# RAM.net
KiCad netlist of a schematic drawn in EAGLE
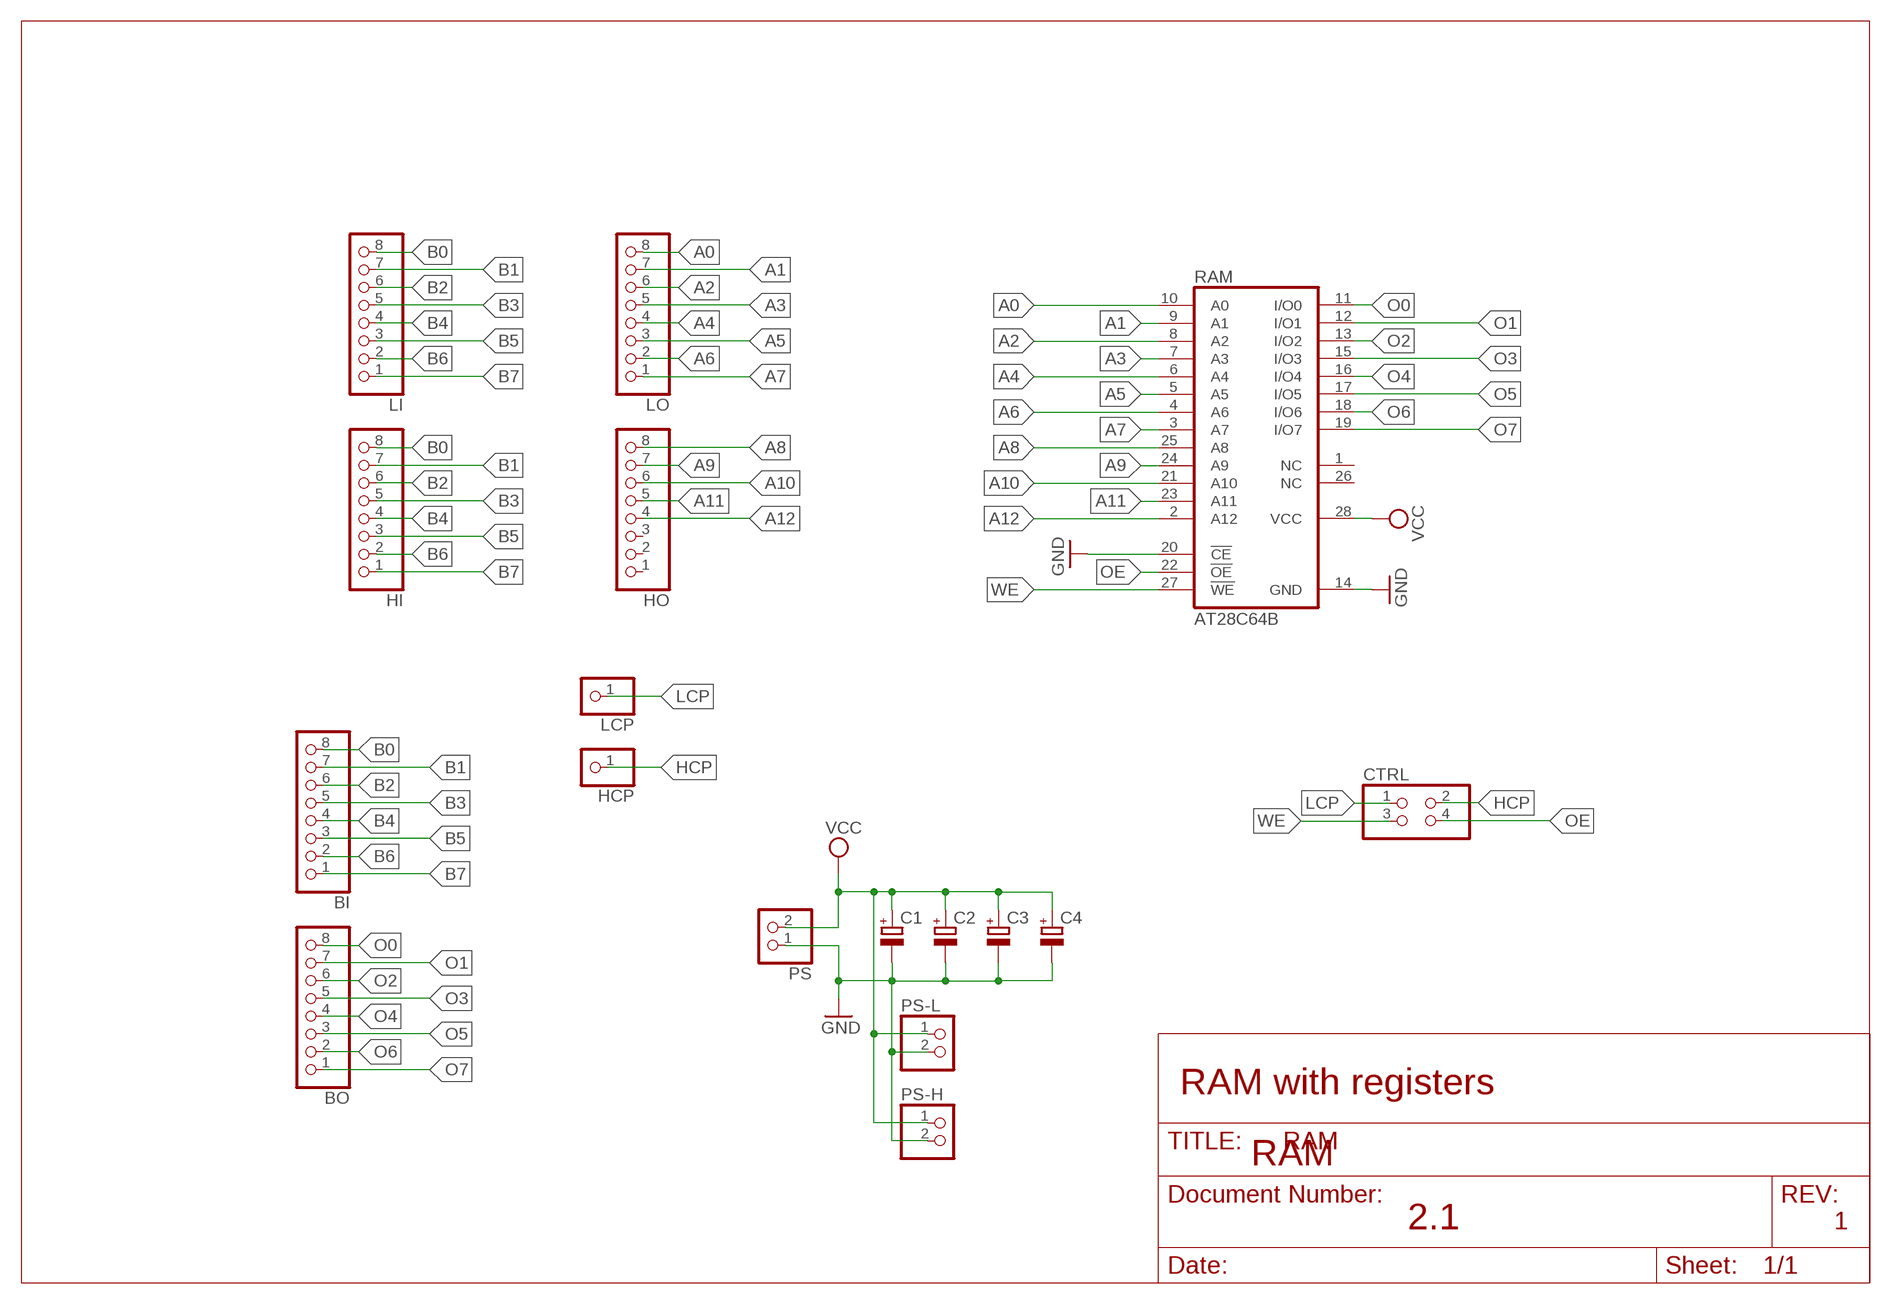
[diagram p0: schematic, sheet 1]

(export (version "E")
  (design (tool "Eeschema 10.0.6"))
  (components
    (comp (ref "BI")
      (value "PINHD-1X8")
      (footprint "eagle-import:1X08")
      (libsource (lib "eagle-import") (part "PINHD-1X8"))
    )
    (comp (ref "BO")
      (value "PINHD-1X8")
      (footprint "eagle-import:1X08")
      (libsource (lib "eagle-import") (part "PINHD-1X8"))
    )
    (comp (ref "C1")
      (value "CPOL-EUE2.5-6")
      (footprint "eagle-import:E2,5-6")
      (libsource (lib "eagle-import") (part "CPOL-EUE2.5-6"))
    )
    (comp (ref "C2")
      (value "CPOL-EUE2.5-6")
      (footprint "eagle-import:E2,5-6")
      (libsource (lib "eagle-import") (part "CPOL-EUE2.5-6"))
    )
    (comp (ref "C3")
      (value "CPOL-EUE2.5-6")
      (footprint "eagle-import:E2,5-6")
      (libsource (lib "eagle-import") (part "CPOL-EUE2.5-6"))
    )
    (comp (ref "C4")
      (value "CPOL-EUE2.5-6")
      (footprint "eagle-import:E2,5-6")
      (libsource (lib "eagle-import") (part "CPOL-EUE2.5-6"))
    )
    (comp (ref "CTRL")
      (value "PINHD-2X2")
      (footprint "eagle-import:2X02")
      (libsource (lib "eagle-import") (part "PINHD-2X2"))
    )
    (comp (ref "HCP")
      (value "PINHD-1X1")
      (footprint "eagle-import:1X01")
      (libsource (lib "eagle-import") (part "PINHD-1X1"))
    )
    (comp (ref "HI")
      (value "PINHD-1X8")
      (footprint "eagle-import:1X08")
      (libsource (lib "eagle-import") (part "PINHD-1X8"))
    )
    (comp (ref "HO")
      (value "PINHD-1X8")
      (footprint "eagle-import:1X08")
      (libsource (lib "eagle-import") (part "PINHD-1X8"))
    )
    (comp (ref "LCP")
      (value "PINHD-1X1")
      (footprint "eagle-import:1X01")
      (libsource (lib "eagle-import") (part "PINHD-1X1"))
    )
    (comp (ref "LI")
      (value "PINHD-1X8")
      (footprint "eagle-import:1X08")
      (libsource (lib "eagle-import") (part "PINHD-1X8"))
    )
    (comp (ref "LO")
      (value "PINHD-1X8")
      (footprint "eagle-import:1X08")
      (libsource (lib "eagle-import") (part "PINHD-1X8"))
    )
    (comp (ref "PS")
      (value "PINHD-1X2")
      (footprint "eagle-import:1X02")
      (libsource (lib "eagle-import") (part "PINHD-1X2"))
    )
    (comp (ref "PS-H")
      (value "PINHD-1X2")
      (footprint "eagle-import:1X02")
      (libsource (lib "eagle-import") (part "PINHD-1X2"))
    )
    (comp (ref "PS-L")
      (value "PINHD-1X2")
      (footprint "eagle-import:1X02")
      (libsource (lib "eagle-import") (part "PINHD-1X2"))
    )
    (comp (ref "RAM")
      (value "AT28C64B")
      (footprint "eagle-import:DIL28-6")
      (fields (field (name "MPN") "AT28C64B-15PU"))
      (libsource (lib "eagle-import") (part "28C64C"))
    )
  )
  (nets
    (net (code "1") (name "A0") (class "Default")
      (node (ref "LO") (pin "8") (pinfunction "8_8") (pintype "passive"))
      (node (ref "RAM") (pin "10") (pinfunction "A0_10") (pintype "input"))
    )
    (net (code "2") (name "A1") (class "Default")
      (node (ref "LO") (pin "7") (pinfunction "7_7") (pintype "passive"))
      (node (ref "RAM") (pin "9") (pinfunction "A1_9") (pintype "input"))
    )
    (net (code "3") (name "A2") (class "Default")
      (node (ref "LO") (pin "6") (pinfunction "6_6") (pintype "passive"))
      (node (ref "RAM") (pin "8") (pinfunction "A2_8") (pintype "input"))
    )
    (net (code "4") (name "A3") (class "Default")
      (node (ref "LO") (pin "5") (pinfunction "5_5") (pintype "passive"))
      (node (ref "RAM") (pin "7") (pinfunction "A3_7") (pintype "input"))
    )
    (net (code "5") (name "A4") (class "Default")
      (node (ref "LO") (pin "4") (pinfunction "4_4") (pintype "passive"))
      (node (ref "RAM") (pin "6") (pinfunction "A4_6") (pintype "input"))
    )
    (net (code "6") (name "A5") (class "Default")
      (node (ref "LO") (pin "3") (pinfunction "3_3") (pintype "passive"))
      (node (ref "RAM") (pin "5") (pinfunction "A5_5") (pintype "input"))
    )
    (net (code "7") (name "A6") (class "Default")
      (node (ref "LO") (pin "2") (pinfunction "2_2") (pintype "passive"))
      (node (ref "RAM") (pin "4") (pinfunction "A6_4") (pintype "input"))
    )
    (net (code "8") (name "A7") (class "Default")
      (node (ref "LO") (pin "1") (pinfunction "1_1") (pintype "passive"))
      (node (ref "RAM") (pin "3") (pinfunction "A7_3") (pintype "input"))
    )
    (net (code "9") (name "A8") (class "Default")
      (node (ref "HO") (pin "8") (pinfunction "8_8") (pintype "passive"))
      (node (ref "RAM") (pin "25") (pinfunction "A8_25") (pintype "input"))
    )
    (net (code "10") (name "A9") (class "Default")
      (node (ref "HO") (pin "7") (pinfunction "7_7") (pintype "passive"))
      (node (ref "RAM") (pin "24") (pinfunction "A9_24") (pintype "input"))
    )
    (net (code "11") (name "A10") (class "Default")
      (node (ref "HO") (pin "6") (pinfunction "6_6") (pintype "passive"))
      (node (ref "RAM") (pin "21") (pinfunction "A10_21") (pintype "input"))
    )
    (net (code "12") (name "A11") (class "Default")
      (node (ref "HO") (pin "5") (pinfunction "5_5") (pintype "passive"))
      (node (ref "RAM") (pin "23") (pinfunction "A11_23") (pintype "input"))
    )
    (net (code "13") (name "A12") (class "Default")
      (node (ref "HO") (pin "4") (pinfunction "4_4") (pintype "passive"))
      (node (ref "RAM") (pin "2") (pinfunction "A12_2") (pintype "input"))
    )
    (net (code "14") (name "B0") (class "Default")
      (node (ref "BI") (pin "8") (pinfunction "8_8") (pintype "passive"))
      (node (ref "HI") (pin "8") (pinfunction "8_8") (pintype "passive"))
      (node (ref "LI") (pin "8") (pinfunction "8_8") (pintype "passive"))
    )
    (net (code "15") (name "B1") (class "Default")
      (node (ref "BI") (pin "7") (pinfunction "7_7") (pintype "passive"))
      (node (ref "HI") (pin "7") (pinfunction "7_7") (pintype "passive"))
      (node (ref "LI") (pin "7") (pinfunction "7_7") (pintype "passive"))
    )
    (net (code "16") (name "B2") (class "Default")
      (node (ref "BI") (pin "6") (pinfunction "6_6") (pintype "passive"))
      (node (ref "HI") (pin "6") (pinfunction "6_6") (pintype "passive"))
      (node (ref "LI") (pin "6") (pinfunction "6_6") (pintype "passive"))
    )
    (net (code "17") (name "B3") (class "Default")
      (node (ref "BI") (pin "5") (pinfunction "5_5") (pintype "passive"))
      (node (ref "HI") (pin "5") (pinfunction "5_5") (pintype "passive"))
      (node (ref "LI") (pin "5") (pinfunction "5_5") (pintype "passive"))
    )
    (net (code "18") (name "B4") (class "Default")
      (node (ref "BI") (pin "4") (pinfunction "4_4") (pintype "passive"))
      (node (ref "HI") (pin "4") (pinfunction "4_4") (pintype "passive"))
      (node (ref "LI") (pin "4") (pinfunction "4_4") (pintype "passive"))
    )
    (net (code "19") (name "B5") (class "Default")
      (node (ref "BI") (pin "3") (pinfunction "3_3") (pintype "passive"))
      (node (ref "HI") (pin "3") (pinfunction "3_3") (pintype "passive"))
      (node (ref "LI") (pin "3") (pinfunction "3_3") (pintype "passive"))
    )
    (net (code "20") (name "B6") (class "Default")
      (node (ref "BI") (pin "2") (pinfunction "2_2") (pintype "passive"))
      (node (ref "HI") (pin "2") (pinfunction "2_2") (pintype "passive"))
      (node (ref "LI") (pin "2") (pinfunction "2_2") (pintype "passive"))
    )
    (net (code "21") (name "B7") (class "Default")
      (node (ref "BI") (pin "1") (pinfunction "1_1") (pintype "passive"))
      (node (ref "HI") (pin "1") (pinfunction "1_1") (pintype "passive"))
      (node (ref "LI") (pin "1") (pinfunction "1_1") (pintype "passive"))
    )
    (net (code "22") (name "GND") (class "Default")
      (node (ref "C1") (pin "-") (pinfunction "-_-") (pintype "passive"))
      (node (ref "C2") (pin "-") (pinfunction "-_-") (pintype "passive"))
      (node (ref "C3") (pin "-") (pinfunction "-_-") (pintype "passive"))
      (node (ref "C4") (pin "-") (pinfunction "-_-") (pintype "passive"))
      (node (ref "PS") (pin "1") (pinfunction "1_1") (pintype "passive"))
      (node (ref "PS-H") (pin "2") (pinfunction "2_2") (pintype "passive"))
      (node (ref "PS-L") (pin "2") (pinfunction "2_2") (pintype "passive"))
      (node (ref "RAM") (pin "14") (pinfunction "GND_14") (pintype "power_in"))
      (node (ref "RAM") (pin "20") (pinfunction "~{CE}_20") (pintype "input"))
    )
    (net (code "23") (name "HCP") (class "Default")
      (node (ref "CTRL") (pin "2") (pinfunction "2_2") (pintype "passive"))
      (node (ref "HCP") (pin "1") (pinfunction "1_1") (pintype "passive"))
    )
    (net (code "24") (name "LCP") (class "Default")
      (node (ref "CTRL") (pin "1") (pinfunction "1_1") (pintype "passive"))
      (node (ref "LCP") (pin "1") (pinfunction "1_1") (pintype "passive"))
    )
    (net (code "25") (name "O0") (class "Default")
      (node (ref "BO") (pin "8") (pinfunction "8_8") (pintype "passive"))
      (node (ref "RAM") (pin "11") (pinfunction "I/O0_11") (pintype "bidirectional"))
    )
    (net (code "26") (name "O1") (class "Default")
      (node (ref "BO") (pin "7") (pinfunction "7_7") (pintype "passive"))
      (node (ref "RAM") (pin "12") (pinfunction "I/O1_12") (pintype "bidirectional"))
    )
    (net (code "27") (name "O2") (class "Default")
      (node (ref "BO") (pin "6") (pinfunction "6_6") (pintype "passive"))
      (node (ref "RAM") (pin "13") (pinfunction "I/O2_13") (pintype "bidirectional"))
    )
    (net (code "28") (name "O3") (class "Default")
      (node (ref "BO") (pin "5") (pinfunction "5_5") (pintype "passive"))
      (node (ref "RAM") (pin "15") (pinfunction "I/O3_15") (pintype "bidirectional"))
    )
    (net (code "29") (name "O4") (class "Default")
      (node (ref "BO") (pin "4") (pinfunction "4_4") (pintype "passive"))
      (node (ref "RAM") (pin "16") (pinfunction "I/O4_16") (pintype "bidirectional"))
    )
    (net (code "30") (name "O5") (class "Default")
      (node (ref "BO") (pin "3") (pinfunction "3_3") (pintype "passive"))
      (node (ref "RAM") (pin "17") (pinfunction "I/O5_17") (pintype "bidirectional"))
    )
    (net (code "31") (name "O6") (class "Default")
      (node (ref "BO") (pin "2") (pinfunction "2_2") (pintype "passive"))
      (node (ref "RAM") (pin "18") (pinfunction "I/O6_18") (pintype "bidirectional"))
    )
    (net (code "32") (name "O7") (class "Default")
      (node (ref "BO") (pin "1") (pinfunction "1_1") (pintype "passive"))
      (node (ref "RAM") (pin "19") (pinfunction "I/O7_19") (pintype "bidirectional"))
    )
    (net (code "33") (name "OE") (class "Default")
      (node (ref "CTRL") (pin "4") (pinfunction "4_4") (pintype "passive"))
      (node (ref "RAM") (pin "22") (pinfunction "~{OE}_22") (pintype "input"))
    )
    (net (code "34") (name "VCC") (class "Default")
      (node (ref "C1") (pin "+") (pinfunction "+_+") (pintype "passive"))
      (node (ref "C2") (pin "+") (pinfunction "+_+") (pintype "passive"))
      (node (ref "C3") (pin "+") (pinfunction "+_+") (pintype "passive"))
      (node (ref "C4") (pin "+") (pinfunction "+_+") (pintype "passive"))
      (node (ref "PS") (pin "2") (pinfunction "2_2") (pintype "passive"))
      (node (ref "PS-H") (pin "1") (pinfunction "1_1") (pintype "passive"))
      (node (ref "PS-L") (pin "1") (pinfunction "1_1") (pintype "passive"))
      (node (ref "RAM") (pin "28") (pinfunction "VCC_28") (pintype "power_in"))
    )
    (net (code "35") (name "WE") (class "Default")
      (node (ref "CTRL") (pin "3") (pinfunction "3_3") (pintype "passive"))
      (node (ref "RAM") (pin "27") (pinfunction "~{WE}_27") (pintype "input"))
    )
    (net (code "36") (name "unconnected-(HO-Pad1)") (class "Default")
      (node (ref "HO") (pin "1") (pinfunction "1_1") (pintype "passive"))
    )
    (net (code "37") (name "unconnected-(HO-Pad2)") (class "Default")
      (node (ref "HO") (pin "2") (pinfunction "2_2") (pintype "passive"))
    )
    (net (code "38") (name "unconnected-(HO-Pad3)") (class "Default")
      (node (ref "HO") (pin "3") (pinfunction "3_3") (pintype "passive"))
    )
    (net (code "39") (name "unconnected-(RAM-NC-Pad1)") (class "Default")
      (node (ref "RAM") (pin "1") (pinfunction "NC_1") (pintype "no_connect"))
    )
    (net (code "40") (name "unconnected-(RAM-NC-Pad26)") (class "Default")
      (node (ref "RAM") (pin "26") (pinfunction "NC_26") (pintype "no_connect"))
    )
  )
)
